# MISTERCRT_Final.net
KiCad netlist of a schematic drawn in EAGLE
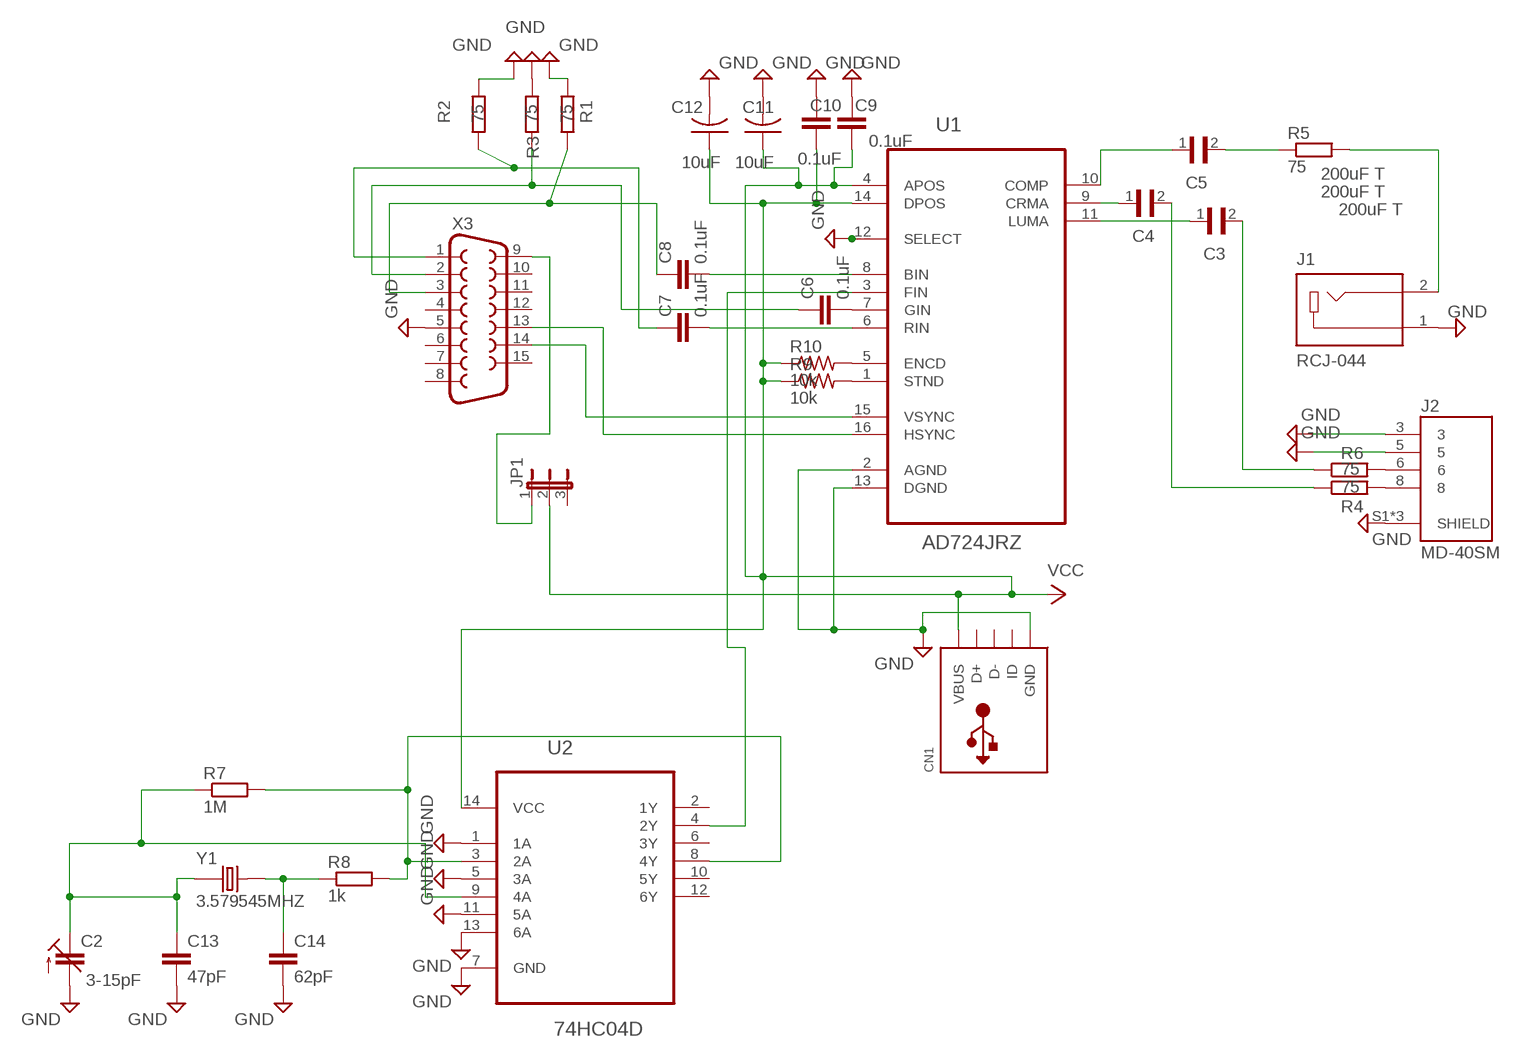
[diagram p0: schematic, sheet 1]

(export (version "E")
  (design (tool "Eeschema 10.0.6"))
  (components
    (comp (ref "C2")
      (value "3-15pF")
      (footprint "eagle-import:CTRIM3018_11")
      (libsource (lib "eagle-import") (part "C-TRIMM3018_11"))
    )
    (comp (ref "C3")
      (value "200uF T")
      (footprint "eagle-import:CAPMP7343X430N")
      (fields (field (name "MF") "KEMET") (field (name "MP") "T491X106K050AT"))
      (libsource (lib "eagle-import") (part "T491X106K050AT"))
    )
    (comp (ref "C4")
      (value "200uF T")
      (footprint "eagle-import:CAPMP7343X430N")
      (fields (field (name "MF") "KEMET") (field (name "MP") "T491X106K050AT"))
      (libsource (lib "eagle-import") (part "T491X106K050AT"))
    )
    (comp (ref "C5")
      (value "200uF T")
      (footprint "eagle-import:CAPMP7343X430N")
      (fields (field (name "MF") "KEMET") (field (name "MP") "T491X106K050AT"))
      (libsource (lib "eagle-import") (part "T491X106K050AT"))
    )
    (comp (ref "C6")
      (value "0.1uF")
      (footprint "eagle-import:C0805")
      (libsource (lib "eagle-import") (part "C-EUC0805"))
    )
    (comp (ref "C7")
      (value "0.1uF")
      (footprint "eagle-import:C0805")
      (libsource (lib "eagle-import") (part "C-EUC0805"))
    )
    (comp (ref "C8")
      (value "0.1uF")
      (footprint "eagle-import:C0805")
      (libsource (lib "eagle-import") (part "C-EUC0805"))
    )
    (comp (ref "C9")
      (value "0.1uF")
      (footprint "eagle-import:C0805")
      (libsource (lib "eagle-import") (part "C-EUC0805"))
    )
    (comp (ref "C10")
      (value "0.1uF")
      (footprint "eagle-import:C0805")
      (libsource (lib "eagle-import") (part "C-EUC0805"))
    )
    (comp (ref "C11")
      (value "10uF")
      (footprint "eagle-import:C1206K")
      (libsource (lib "eagle-import") (part "C-USC1206K"))
    )
    (comp (ref "C12")
      (value "10uF")
      (footprint "eagle-import:C1206K")
      (libsource (lib "eagle-import") (part "C-USC1206K"))
    )
    (comp (ref "C13")
      (value "47pF")
      (footprint "eagle-import:C0805")
      (libsource (lib "eagle-import") (part "C-EUC0805"))
    )
    (comp (ref "C14")
      (value "62pF")
      (footprint "eagle-import:C0805")
      (libsource (lib "eagle-import") (part "C-EUC0805"))
    )
    (comp (ref "CN1")
      (value "USBMINIB")
      (footprint "eagle-import:USB-MINIB")
      (libsource (lib "eagle-import") (part "USBMINIB"))
    )
    (comp (ref "J1")
      (value "RCJ-044")
      (footprint "eagle-import:CUI_RCJ-044")
      (fields (field (name "MANUFACTURER") "CUI Devices"))
      (libsource (lib "eagle-import") (part "RCJ-044"))
    )
    (comp (ref "J2")
      (value "MD-40SM")
      (footprint "eagle-import:CUI_MD-40SM")
      (fields (field (name "MANUFACTURER") "CUI Devices"))
      (libsource (lib "eagle-import") (part "MD-40SM"))
    )
    (comp (ref "JP1")
      (value "JP2W")
      (footprint "eagle-import:JP2W")
      (libsource (lib "eagle-import") (part "JP2W"))
    )
    (comp (ref "R1")
      (value "75")
      (footprint "eagle-import:M0805")
      (libsource (lib "eagle-import") (part "R-EU_M0805"))
    )
    (comp (ref "R2")
      (value "75")
      (footprint "eagle-import:M0805")
      (libsource (lib "eagle-import") (part "R-EU_M0805"))
    )
    (comp (ref "R3")
      (value "75")
      (footprint "eagle-import:M0805")
      (libsource (lib "eagle-import") (part "R-EU_M0805"))
    )
    (comp (ref "R4")
      (value "75")
      (footprint "eagle-import:M0805")
      (libsource (lib "eagle-import") (part "R-EU_M0805"))
    )
    (comp (ref "R5")
      (value "75")
      (footprint "eagle-import:M0805")
      (libsource (lib "eagle-import") (part "R-EU_M0805"))
    )
    (comp (ref "R6")
      (value "75")
      (footprint "eagle-import:M0805")
      (libsource (lib "eagle-import") (part "R-EU_M0805"))
    )
    (comp (ref "R7")
      (value "1M")
      (footprint "eagle-import:R2512")
      (libsource (lib "eagle-import") (part "R-EU_R2512"))
    )
    (comp (ref "R8")
      (value "1k")
      (footprint "eagle-import:R0805")
      (libsource (lib "eagle-import") (part "rcl_334_R-EU_R0805"))
    )
    (comp (ref "R9")
      (value "10k")
      (footprint "eagle-import:R0805")
      (libsource (lib "eagle-import") (part "R-US_R0805"))
    )
    (comp (ref "R10")
      (value "10k")
      (footprint "eagle-import:R0805")
      (libsource (lib "eagle-import") (part "R-US_R0805"))
    )
    (comp (ref "U1")
      (value "AD724JRZ")
      (footprint "eagle-import:SOIC127P1032X265-16N")
      (fields (field (name "DIGI-KEY_PART_NUMBER") "AD724JRZ-ND") (field (name "MF") "Analog Devices"))
      (libsource (lib "eagle-import") (part "AD724JRZ"))
    )
    (comp (ref "U2")
      (value "74HC04D")
      (footprint "eagle-import:SOIC127P600X175-14N")
      (fields (field (name "MF") "Toshiba"))
      (libsource (lib "eagle-import") (part "74HC04D"))
    )
    (comp (ref "X3")
      (value "F15HDH")
      (footprint "eagle-import:HDF15H")
      (libsource (lib "eagle-import") (part "F15HDH"))
    )
    (comp (ref "Y1")
      (value "3.579545MHZ")
      (footprint "eagle-import:XTAL_ECS-35-17-18-TR")
      (fields
        (field (name "DIGI-KEY_PART_NUMBER") "XC584CT-ND")
        (field (name "MF") "ECS Inc.")
        (field (name "MP") "ECS-35-17-18-TR")
      )
      (libsource (lib "eagle-import") (part "ECS-35-17-18-TR"))
    )
  )
  (nets
    (net (code "1") (name "GND") (class "Default")
      (node (ref "C10") (pin "2") (pinfunction "2_2") (pintype "passive"))
      (node (ref "C11") (pin "2") (pinfunction "2_2") (pintype "passive"))
      (node (ref "C12") (pin "2") (pinfunction "2_2") (pintype "passive"))
      (node (ref "C13") (pin "2") (pinfunction "2_2") (pintype "passive"))
      (node (ref "C14") (pin "2") (pinfunction "2_2") (pintype "passive"))
      (node (ref "C2") (pin "-") (pinfunction "A_-") (pintype "passive"))
      (node (ref "C9") (pin "2") (pinfunction "2_2") (pintype "passive"))
      (node (ref "CN1") (pin "GND") (pinfunction "GND_GND") (pintype "power_in"))
      (node (ref "J1") (pin "1") (pinfunction "1_1") (pintype "passive"))
      (node (ref "J2") (pin "3") (pinfunction "3_3") (pintype "passive"))
      (node (ref "J2") (pin "5") (pinfunction "5_5") (pintype "passive"))
      (node (ref "J2") (pin "S1") (pinfunction "SHIELD_S1") (pintype "passive"))
      (node (ref "J2") (pin "S2") (pinfunction "SHIELD_S2") (pintype "passive"))
      (node (ref "J2") (pin "S3") (pinfunction "SHIELD_S3") (pintype "passive"))
      (node (ref "R1") (pin "2") (pinfunction "2_2") (pintype "passive"))
      (node (ref "R2") (pin "2") (pinfunction "2_2") (pintype "passive"))
      (node (ref "R3") (pin "2") (pinfunction "2_2") (pintype "passive"))
      (node (ref "U1") (pin "12") (pinfunction "SELECT_12") (pintype "input"))
      (node (ref "U1") (pin "13") (pinfunction "DGND_13") (pintype "passive"))
      (node (ref "U1") (pin "2") (pinfunction "AGND_2") (pintype "passive"))
      (node (ref "U2") (pin "1") (pinfunction "1A_1") (pintype "input"))
      (node (ref "U2") (pin "11") (pinfunction "5A_11") (pintype "input"))
      (node (ref "U2") (pin "13") (pinfunction "6A_13") (pintype "input"))
      (node (ref "U2") (pin "5") (pinfunction "3A_5") (pintype "input"))
      (node (ref "U2") (pin "7") (pinfunction "GND_7") (pintype "passive"))
      (node (ref "X3") (pin "5") (pinfunction "5_5") (pintype "passive"))
    )
    (net (code "2") (name "Net-(C2-E)") (class "Default")
      (node (ref "C13") (pin "1") (pinfunction "1_1") (pintype "passive"))
      (node (ref "C2") (pin "+") (pinfunction "E_+") (pintype "passive"))
      (node (ref "R7") (pin "1") (pinfunction "1_1") (pintype "passive"))
      (node (ref "U2") (pin "9") (pinfunction "4A_9") (pintype "input"))
      (node (ref "Y1") (pin "1") (pinfunction "1_1") (pintype "passive"))
      (node (ref "Y1") (pin "4") (pinfunction "1_4") (pintype "passive"))
    )
    (net (code "3") (name "Net-(C3-Pad2)") (class "Default")
      (node (ref "C3") (pin "2") (pinfunction "2_2") (pintype "passive"))
      (node (ref "R6") (pin "1") (pinfunction "1_1") (pintype "passive"))
    )
    (net (code "4") (name "Net-(C4-Pad2)") (class "Default")
      (node (ref "C4") (pin "2") (pinfunction "2_2") (pintype "passive"))
      (node (ref "R4") (pin "1") (pinfunction "1_1") (pintype "passive"))
    )
    (net (code "5") (name "Net-(C5-Pad2)") (class "Default")
      (node (ref "C5") (pin "2") (pinfunction "2_2") (pintype "passive"))
      (node (ref "R5") (pin "1") (pinfunction "1_1") (pintype "passive"))
    )
    (net (code "6") (name "Net-(C6-Pad1)") (class "Default")
      (node (ref "C6") (pin "1") (pinfunction "1_1") (pintype "passive"))
      (node (ref "R3") (pin "1") (pinfunction "1_1") (pintype "passive"))
      (node (ref "X3") (pin "2") (pinfunction "2_2") (pintype "passive"))
    )
    (net (code "7") (name "Net-(C7-Pad1)") (class "Default")
      (node (ref "C7") (pin "1") (pinfunction "1_1") (pintype "passive"))
      (node (ref "R2") (pin "1") (pinfunction "1_1") (pintype "passive"))
      (node (ref "X3") (pin "1") (pinfunction "1_1") (pintype "passive"))
    )
    (net (code "8") (name "Net-(C8-Pad1)") (class "Default")
      (node (ref "C8") (pin "1") (pinfunction "1_1") (pintype "passive"))
      (node (ref "R1") (pin "1") (pinfunction "1_1") (pintype "passive"))
      (node (ref "X3") (pin "3") (pinfunction "3_3") (pintype "passive"))
    )
    (net (code "9") (name "Net-(C14-Pad1)") (class "Default")
      (node (ref "C14") (pin "1") (pinfunction "1_1") (pintype "passive"))
      (node (ref "R8") (pin "1") (pinfunction "1_1") (pintype "passive"))
      (node (ref "Y1") (pin "2") (pinfunction "2_2") (pintype "passive"))
      (node (ref "Y1") (pin "3") (pinfunction "2_3") (pintype "passive"))
    )
    (net (code "10") (name "Net-(J1-Pad2)") (class "Default")
      (node (ref "J1") (pin "2") (pinfunction "2_2") (pintype "passive"))
      (node (ref "R5") (pin "2") (pinfunction "2_2") (pintype "passive"))
    )
    (net (code "11") (name "Net-(J2-Pad6)") (class "Default")
      (node (ref "J2") (pin "6") (pinfunction "6_6") (pintype "passive"))
      (node (ref "R6") (pin "2") (pinfunction "2_2") (pintype "passive"))
    )
    (net (code "12") (name "Net-(J2-Pad8)") (class "Default")
      (node (ref "J2") (pin "8") (pinfunction "8_8") (pintype "passive"))
      (node (ref "R4") (pin "2") (pinfunction "2_2") (pintype "passive"))
    )
    (net (code "13") (name "Net-(JP1-Pad1)") (class "Default")
      (node (ref "JP1") (pin "1") (pinfunction "1_1") (pintype "passive"))
      (node (ref "X3") (pin "9") (pinfunction "9_9") (pintype "passive"))
    )
    (net (code "14") (name "Net-(U1-BIN)") (class "Default")
      (node (ref "C8") (pin "2") (pinfunction "2_2") (pintype "passive"))
      (node (ref "U1") (pin "8") (pinfunction "BIN_8") (pintype "input"))
    )
    (net (code "15") (name "Net-(U1-COMP)") (class "Default")
      (node (ref "C5") (pin "1") (pinfunction "1_1") (pintype "passive"))
      (node (ref "U1") (pin "10") (pinfunction "COMP_10") (pintype "output"))
    )
    (net (code "16") (name "Net-(U1-CRMA)") (class "Default")
      (node (ref "C4") (pin "1") (pinfunction "1_1") (pintype "passive"))
      (node (ref "U1") (pin "9") (pinfunction "CRMA_9") (pintype "output"))
    )
    (net (code "17") (name "Net-(U1-ENCD)") (class "Default")
      (node (ref "R10") (pin "2") (pinfunction "2_2") (pintype "passive"))
      (node (ref "U1") (pin "5") (pinfunction "ENCD_5") (pintype "input"))
    )
    (net (code "18") (name "Net-(U1-FIN)") (class "Default")
      (node (ref "U1") (pin "3") (pinfunction "FIN_3") (pintype "input"))
      (node (ref "U2") (pin "4") (pinfunction "2Y_4") (pintype "output"))
    )
    (net (code "19") (name "Net-(U1-GIN)") (class "Default")
      (node (ref "C6") (pin "2") (pinfunction "2_2") (pintype "passive"))
      (node (ref "U1") (pin "7") (pinfunction "GIN_7") (pintype "input"))
    )
    (net (code "20") (name "Net-(U1-HSYNC)") (class "Default")
      (node (ref "U1") (pin "16") (pinfunction "HSYNC_16") (pintype "input"))
      (node (ref "X3") (pin "13") (pinfunction "13_13") (pintype "passive"))
    )
    (net (code "21") (name "Net-(U1-LUMA)") (class "Default")
      (node (ref "C3") (pin "1") (pinfunction "1_1") (pintype "passive"))
      (node (ref "U1") (pin "11") (pinfunction "LUMA_11") (pintype "output"))
    )
    (net (code "22") (name "Net-(U1-RIN)") (class "Default")
      (node (ref "C7") (pin "2") (pinfunction "2_2") (pintype "passive"))
      (node (ref "U1") (pin "6") (pinfunction "RIN_6") (pintype "input"))
    )
    (net (code "23") (name "Net-(U1-STND)") (class "Default")
      (node (ref "R9") (pin "2") (pinfunction "2_2") (pintype "passive"))
      (node (ref "U1") (pin "1") (pinfunction "STND_1") (pintype "input"))
    )
    (net (code "24") (name "Net-(U1-VSYNC)") (class "Default")
      (node (ref "U1") (pin "15") (pinfunction "VSYNC_15") (pintype "input"))
      (node (ref "X3") (pin "14") (pinfunction "14_14") (pintype "passive"))
    )
    (net (code "25") (name "Net-(U2-2A)") (class "Default")
      (node (ref "R7") (pin "2") (pinfunction "2_2") (pintype "passive"))
      (node (ref "R8") (pin "2") (pinfunction "2_2") (pintype "passive"))
      (node (ref "U2") (pin "3") (pinfunction "2A_3") (pintype "input"))
      (node (ref "U2") (pin "8") (pinfunction "4Y_8") (pintype "output"))
    )
    (net (code "26") (name "VCC") (class "Default")
      (node (ref "C10") (pin "1") (pinfunction "1_1") (pintype "passive"))
      (node (ref "C11") (pin "1") (pinfunction "1_1") (pintype "passive"))
      (node (ref "C12") (pin "1") (pinfunction "1_1") (pintype "passive"))
      (node (ref "C9") (pin "1") (pinfunction "1_1") (pintype "passive"))
      (node (ref "CN1") (pin "VBUS") (pinfunction "VBUS_VBUS") (pintype "power_in"))
      (node (ref "JP1") (pin "2") (pinfunction "2_2") (pintype "passive"))
      (node (ref "R10") (pin "1") (pinfunction "1_1") (pintype "passive"))
      (node (ref "R9") (pin "1") (pinfunction "1_1") (pintype "passive"))
      (node (ref "U1") (pin "14") (pinfunction "DPOS_14") (pintype "power_in"))
      (node (ref "U1") (pin "4") (pinfunction "APOS_4") (pintype "power_in"))
      (node (ref "U2") (pin "14") (pinfunction "VCC_14") (pintype "power_in"))
    )
    (net (code "27") (name "unconnected-(CN1-PadD+)") (class "Default")
      (node (ref "CN1") (pin "D+") (pinfunction "D+_D+") (pintype "bidirectional"))
    )
    (net (code "28") (name "unconnected-(CN1-PadD-)") (class "Default")
      (node (ref "CN1") (pin "D-") (pinfunction "D-_D-") (pintype "bidirectional"))
    )
    (net (code "29") (name "unconnected-(CN1-PadID)") (class "Default")
      (node (ref "CN1") (pin "ID") (pinfunction "ID_ID") (pintype "bidirectional"))
    )
    (net (code "30") (name "unconnected-(JP1-Pad3)") (class "Default")
      (node (ref "JP1") (pin "3") (pinfunction "3_3") (pintype "passive"))
    )
    (net (code "31") (name "unconnected-(U2-1Y-Pad2)") (class "Default")
      (node (ref "U2") (pin "2") (pinfunction "1Y_2") (pintype "output"))
    )
    (net (code "32") (name "unconnected-(U2-3Y-Pad6)") (class "Default")
      (node (ref "U2") (pin "6") (pinfunction "3Y_6") (pintype "output"))
    )
    (net (code "33") (name "unconnected-(U2-5Y-Pad10)") (class "Default")
      (node (ref "U2") (pin "10") (pinfunction "5Y_10") (pintype "output"))
    )
    (net (code "34") (name "unconnected-(U2-6Y-Pad12)") (class "Default")
      (node (ref "U2") (pin "12") (pinfunction "6Y_12") (pintype "output"))
    )
    (net (code "35") (name "unconnected-(X3-Pad4)") (class "Default")
      (node (ref "X3") (pin "4") (pinfunction "4_4") (pintype "passive"))
    )
    (net (code "36") (name "unconnected-(X3-Pad6)") (class "Default")
      (node (ref "X3") (pin "6") (pinfunction "6_6") (pintype "passive"))
    )
    (net (code "37") (name "unconnected-(X3-Pad7)") (class "Default")
      (node (ref "X3") (pin "7") (pinfunction "7_7") (pintype "passive"))
    )
    (net (code "38") (name "unconnected-(X3-Pad8)") (class "Default")
      (node (ref "X3") (pin "8") (pinfunction "8_8") (pintype "passive"))
    )
    (net (code "39") (name "unconnected-(X3-Pad10)") (class "Default")
      (node (ref "X3") (pin "10") (pinfunction "10_10") (pintype "passive"))
    )
    (net (code "40") (name "unconnected-(X3-Pad11)") (class "Default")
      (node (ref "X3") (pin "11") (pinfunction "11_11") (pintype "passive"))
    )
    (net (code "41") (name "unconnected-(X3-Pad12)") (class "Default")
      (node (ref "X3") (pin "12") (pinfunction "12_12") (pintype "passive"))
    )
    (net (code "42") (name "unconnected-(X3-Pad15)") (class "Default")
      (node (ref "X3") (pin "15") (pinfunction "15_15") (pintype "passive"))
    )
  )
)
